# groovy.net
KiCad netlist of a schematic drawn in EAGLE
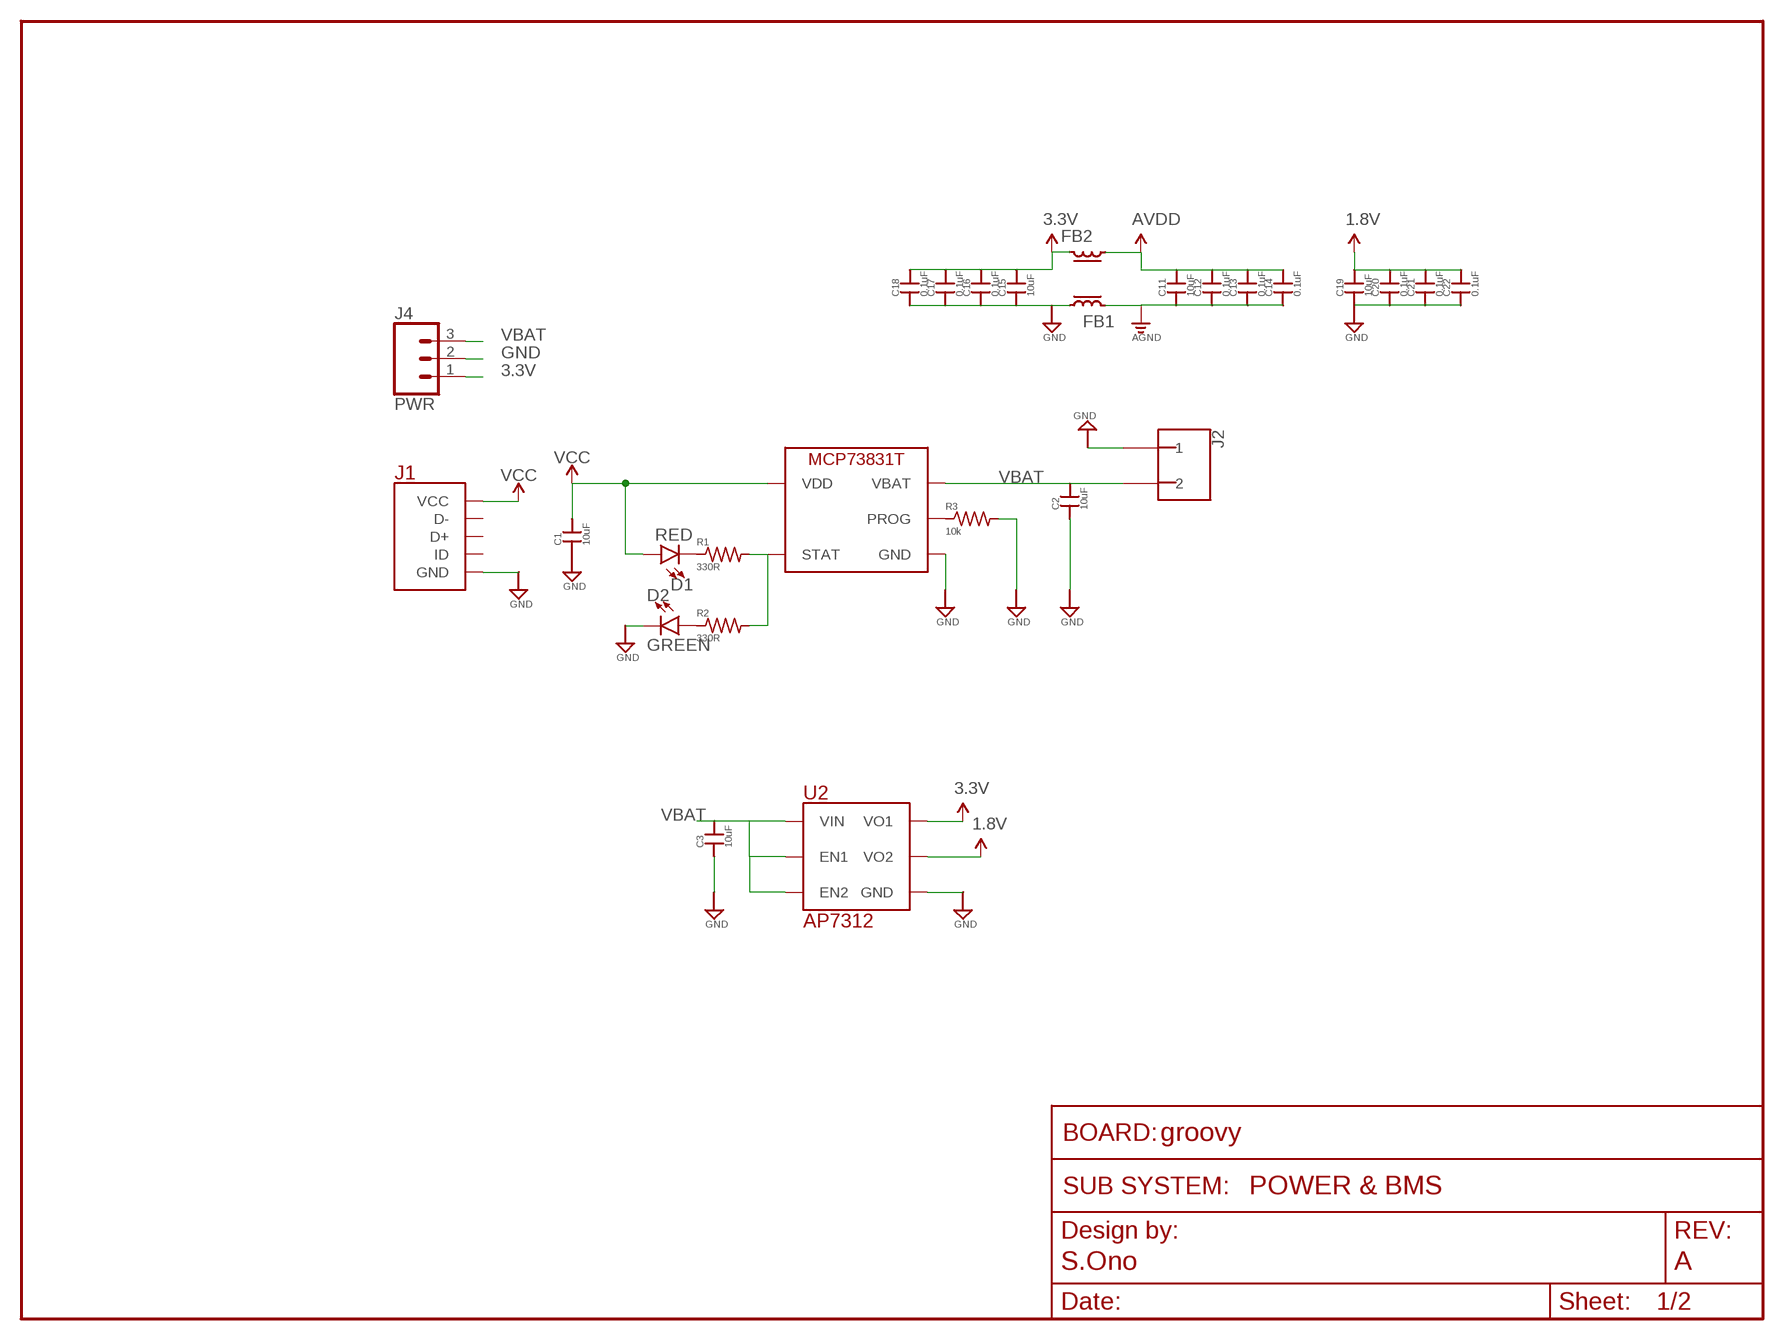
[diagram p0: schematic, sheet 1]
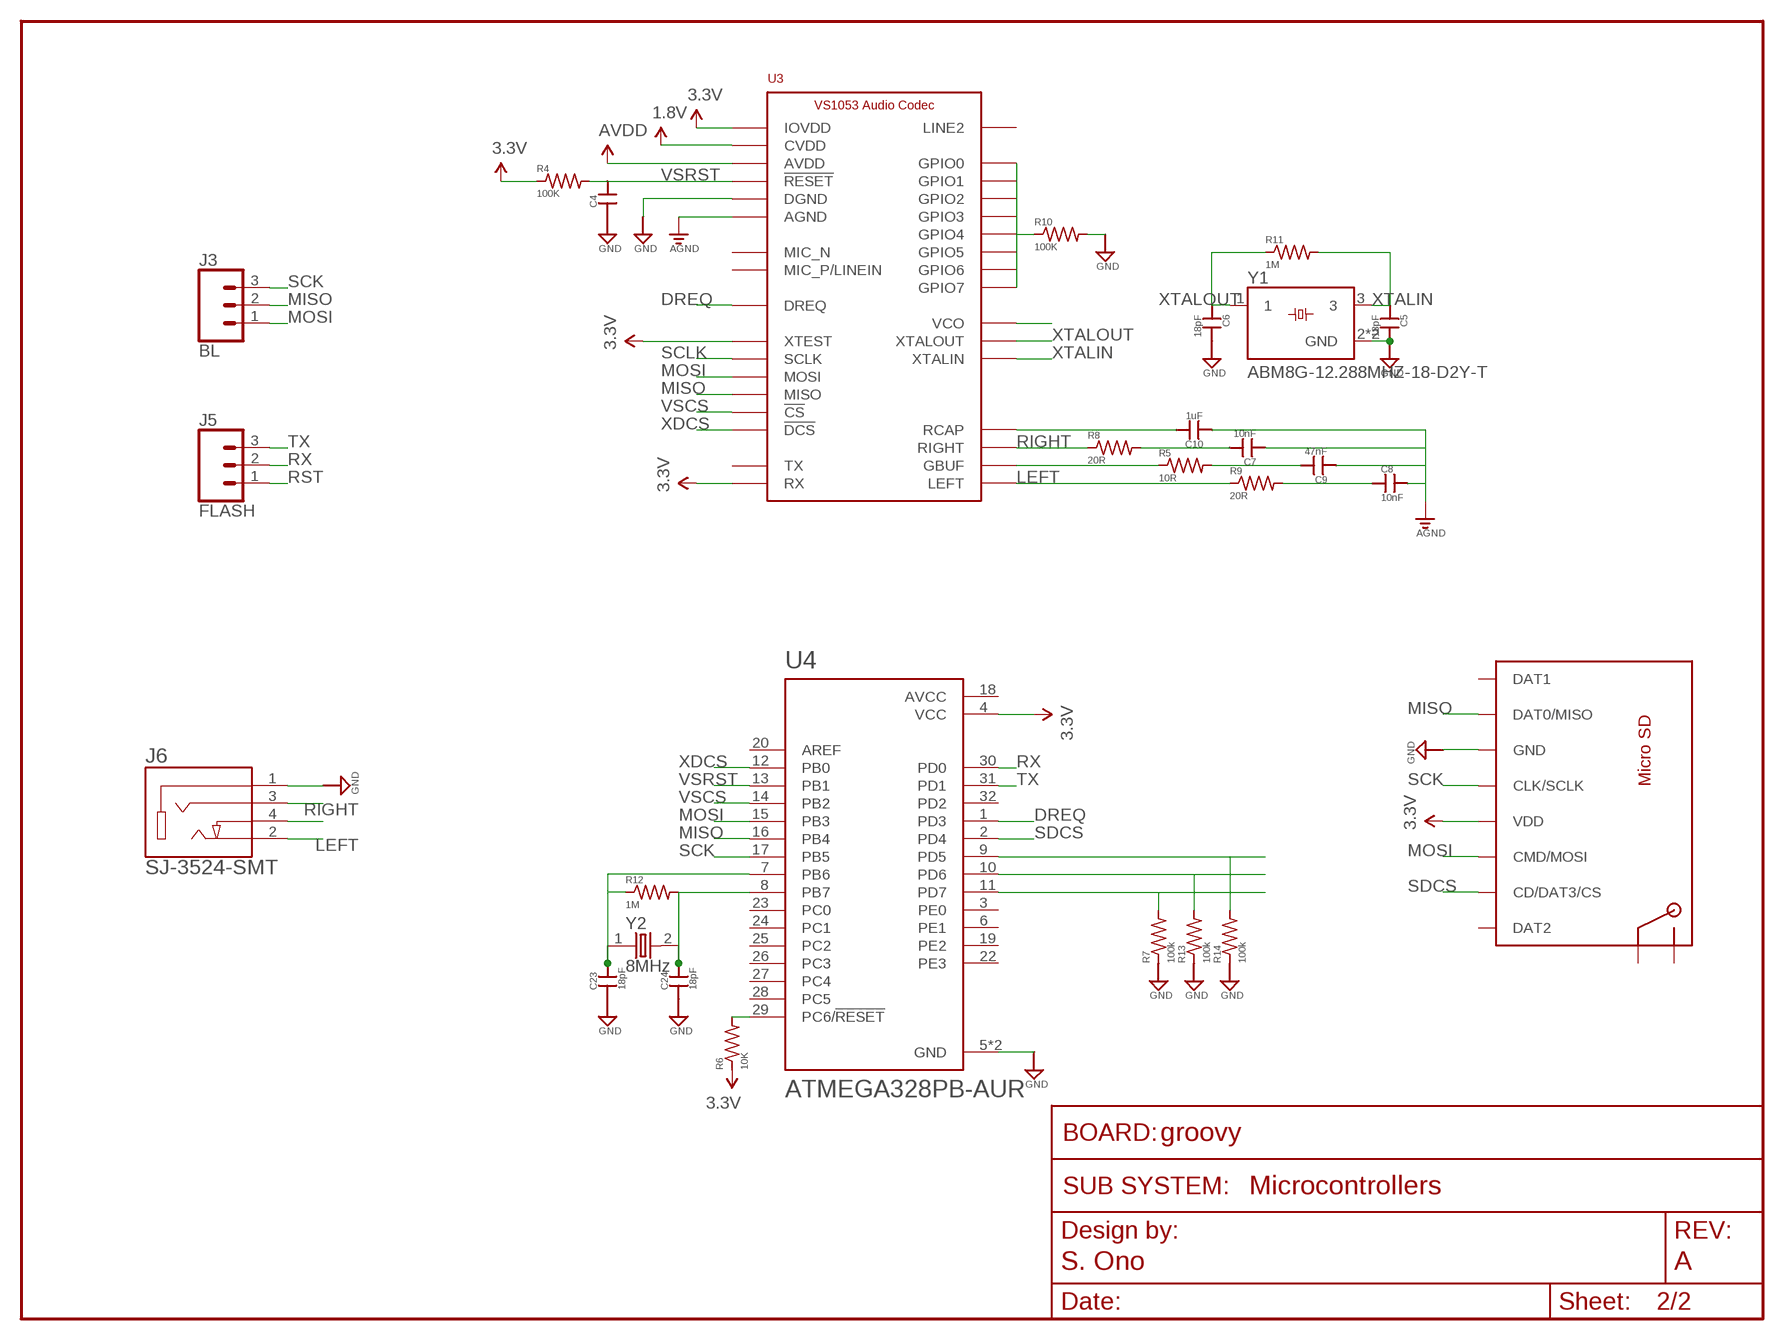
[diagram p1: schematic, sheet 2]

(export (version "E")
  (design (tool "Eeschema 10.0.6"))
  (components
    (comp (ref "C4")
      (value "CAP0603-CAP")
      (footprint "eagle-import:0603-CAP")
      (libsource (lib "eagle-import") (part "CAP0603-CAP"))
    )
    (comp (ref "C5")
      (value "18pF")
      (footprint "eagle-import:0603-CAP")
      (libsource (lib "eagle-import") (part "CAP0603-CAP"))
    )
    (comp (ref "C6")
      (value "18pF")
      (footprint "eagle-import:0603-CAP")
      (libsource (lib "eagle-import") (part "CAP0603-CAP"))
    )
    (comp (ref "C7")
      (value "10nF")
      (footprint "eagle-import:0603-CAP")
      (libsource (lib "eagle-import") (part "CAP0603-CAP"))
    )
    (comp (ref "C8")
      (value "10nF")
      (footprint "eagle-import:0603-CAP")
      (libsource (lib "eagle-import") (part "CAP0603-CAP"))
    )
    (comp (ref "C9")
      (value "47nF")
      (footprint "eagle-import:0603-CAP")
      (libsource (lib "eagle-import") (part "CAP0603-CAP"))
    )
    (comp (ref "C10")
      (value "1uF")
      (footprint "eagle-import:0603-CAP")
      (libsource (lib "eagle-import") (part "CAP0603-CAP"))
    )
    (comp (ref "C23")
      (value "18pF")
      (footprint "eagle-import:0603-CAP")
      (libsource (lib "eagle-import") (part "CAP0603-CAP"))
    )
    (comp (ref "C24")
      (value "18pF")
      (footprint "eagle-import:0603-CAP")
      (libsource (lib "eagle-import") (part "CAP0603-CAP"))
    )
    (comp (ref "J3")
      (value "BL")
      (footprint "eagle-import:1X03")
      (libsource (lib "eagle-import") (part "CONN_03"))
    )
    (comp (ref "J5")
      (value "FLASH")
      (footprint "eagle-import:1X03")
      (libsource (lib "eagle-import") (part "CONN_03"))
    )
    (comp (ref "J6")
      (value "SJ-3524-SMT")
      (footprint "eagle-import:CUI_SJ-3524-SMT")
      (fields
        (field (name "DIGI-KEY_PART_NUMBER") "CP-3524SJCT-ND")
        (field (name "MF") "CUI Inc.")
        (field (name "MP") "SJ-3524-SMT-TR")
      )
      (libsource (lib "eagle-import") (part "SJ-3524-SMT"))
    )
    (comp (ref "P1")
      (value "MICROSD")
      (footprint "eagle-import:MICROSD")
      (libsource (lib "eagle-import") (part "MICROSD"))
    )
    (comp (ref "R4")
      (value "100K")
      (footprint "eagle-import:R0603")
      (fields (field (name "MANUFACTURER") "Rohm Semiconductor"))
      (libsource (lib "eagle-import") (part "R-US_R0603"))
    )
    (comp (ref "R5")
      (value "10R")
      (footprint "eagle-import:R0603")
      (fields (field (name "MANUFACTURER") "Rohm Semiconductor"))
      (libsource (lib "eagle-import") (part "R-US_R0603"))
    )
    (comp (ref "R6")
      (value "10K")
      (footprint "eagle-import:R0603")
      (fields (field (name "MANUFACTURER") "Rohm Semiconductor"))
      (libsource (lib "eagle-import") (part "R-US_R0603"))
    )
    (comp (ref "R7")
      (value "100k")
      (footprint "eagle-import:R0603")
      (fields (field (name "MANUFACTURER") "Rohm Semiconductor"))
      (libsource (lib "eagle-import") (part "R-US_R0603"))
    )
    (comp (ref "R8")
      (value "20R")
      (footprint "eagle-import:R0603")
      (fields (field (name "MANUFACTURER") "Rohm Semiconductor"))
      (libsource (lib "eagle-import") (part "R-US_R0603"))
    )
    (comp (ref "R9")
      (value "20R")
      (footprint "eagle-import:R0603")
      (fields (field (name "MANUFACTURER") "Rohm Semiconductor"))
      (libsource (lib "eagle-import") (part "R-US_R0603"))
    )
    (comp (ref "R10")
      (value "100K")
      (footprint "eagle-import:R0603")
      (fields (field (name "MANUFACTURER") "Rohm Semiconductor"))
      (libsource (lib "eagle-import") (part "R-US_R0603"))
    )
    (comp (ref "R11")
      (value "1M")
      (footprint "eagle-import:R0603")
      (fields (field (name "MANUFACTURER") "Rohm Semiconductor"))
      (libsource (lib "eagle-import") (part "R-US_R0603"))
    )
    (comp (ref "R12")
      (value "1M")
      (footprint "eagle-import:R0603")
      (fields (field (name "MANUFACTURER") "Rohm Semiconductor"))
      (libsource (lib "eagle-import") (part "R-US_R0603"))
    )
    (comp (ref "R13")
      (value "100k")
      (footprint "eagle-import:R0603")
      (fields (field (name "MANUFACTURER") "Rohm Semiconductor"))
      (libsource (lib "eagle-import") (part "R-US_R0603"))
    )
    (comp (ref "R14")
      (value "100k")
      (footprint "eagle-import:R0603")
      (fields (field (name "MANUFACTURER") "Rohm Semiconductor"))
      (libsource (lib "eagle-import") (part "R-US_R0603"))
    )
    (comp (ref "U3")
      (value "VS1053")
      (footprint "eagle-import:QFP50P900X900X120-48N")
      (libsource (lib "eagle-import") (part "VS1053"))
    )
    (comp (ref "U4")
      (value "ATMEGA328PB-AUR")
      (footprint "eagle-import:QFP80P900X900X120-32N")
      (fields (field (name "DIGI-KEY_PART_NUMBER") "ATMEGA328PB-AURCT-ND") (field (name "MF") "Microchip"))
      (libsource (lib "eagle-import") (part "ATMEGA328PB-AUR"))
    )
    (comp (ref "Y1")
      (value "ABM8G-12.288MHZ-18-D2Y-T")
      (footprint "eagle-import:OSCSC320X250X100N")
      (fields (field (name "DIGI-KEY_PART_NUMBER") "535-10262-1-ND") (field (name "MF") "Abracon"))
      (libsource (lib "eagle-import") (part "ABM8G-12.288MHZ-18-D2Y-T"))
    )
    (comp (ref "Y2")
      (value "8MHz")
      (footprint "eagle-import:XTAL500X320X130N")
      (fields
        (field (name "DIGI-KEY_PART_NUMBER") "535-10630-1-ND")
        (field (name "MF") "Abracon")
        (field (name "MP") "ABM3-8.000MHZ-D2Y-T")
      )
      (libsource (lib "eagle-import") (part "ABM3-8.000MHZ-D2Y-T"))
    )
    (comp (ref "C1")
      (value "10uF")
      (footprint "eagle-import:0402-CAP")
      (libsource (lib "eagle-import") (part "CAP0402-CAP"))
    )
    (comp (ref "C2")
      (value "10uF")
      (footprint "eagle-import:0402-CAP")
      (libsource (lib "eagle-import") (part "CAP0402-CAP"))
    )
    (comp (ref "C3")
      (value "10uF")
      (footprint "eagle-import:0402-CAP")
      (libsource (lib "eagle-import") (part "CAP0402-CAP"))
    )
    (comp (ref "C11")
      (value "10uF")
      (footprint "eagle-import:0402-CAP")
      (libsource (lib "eagle-import") (part "CAP0402-CAP"))
    )
    (comp (ref "C12")
      (value "0.1uF")
      (footprint "eagle-import:0402-CAP")
      (libsource (lib "eagle-import") (part "CAP0402-CAP"))
    )
    (comp (ref "C13")
      (value "0.1uF")
      (footprint "eagle-import:0402-CAP")
      (libsource (lib "eagle-import") (part "CAP0402-CAP"))
    )
    (comp (ref "C14")
      (value "0.1uF")
      (footprint "eagle-import:0402-CAP")
      (libsource (lib "eagle-import") (part "CAP0402-CAP"))
    )
    (comp (ref "C15")
      (value "10uF")
      (footprint "eagle-import:0402-CAP")
      (libsource (lib "eagle-import") (part "CAP0402-CAP"))
    )
    (comp (ref "C16")
      (value "0.1uF")
      (footprint "eagle-import:0402-CAP")
      (libsource (lib "eagle-import") (part "CAP0402-CAP"))
    )
    (comp (ref "C17")
      (value "0.1uF")
      (footprint "eagle-import:0402-CAP")
      (libsource (lib "eagle-import") (part "CAP0402-CAP"))
    )
    (comp (ref "C18")
      (value "0.1uF")
      (footprint "eagle-import:0402-CAP")
      (libsource (lib "eagle-import") (part "CAP0402-CAP"))
    )
    (comp (ref "C19")
      (value "10uF")
      (footprint "eagle-import:0402-CAP")
      (libsource (lib "eagle-import") (part "CAP0402-CAP"))
    )
    (comp (ref "C20")
      (value "0.1uF")
      (footprint "eagle-import:0402-CAP")
      (libsource (lib "eagle-import") (part "CAP0402-CAP"))
    )
    (comp (ref "C21")
      (value "0.1uF")
      (footprint "eagle-import:0402-CAP")
      (libsource (lib "eagle-import") (part "CAP0402-CAP"))
    )
    (comp (ref "C22")
      (value "0.1uF")
      (footprint "eagle-import:0402-CAP")
      (libsource (lib "eagle-import") (part "CAP0402-CAP"))
    )
    (comp (ref "D1")
      (value "RED")
      (footprint "eagle-import:LED-0603")
      (libsource (lib "eagle-import") (part "LED0603"))
    )
    (comp (ref "D2")
      (value "GREEN")
      (footprint "eagle-import:LED-0603")
      (libsource (lib "eagle-import") (part "LED0603"))
    )
    (comp (ref "FB1")
      (value "FERRITE")
      (footprint "eagle-import:0603-FERR")
      (libsource (lib "eagle-import") (part "FERRITE"))
    )
    (comp (ref "FB2")
      (value "FERRITE")
      (footprint "eagle-import:0603-FERR")
      (libsource (lib "eagle-import") (part "FERRITE"))
    )
    (comp (ref "J1")
      (value "USB_MICRO")
      (footprint "eagle-import:USB_MICRO")
      (libsource (lib "eagle-import") (part "USB_MICRO"))
    )
    (comp (ref "J2")
      (value "2_PIN_JST-XH")
      (footprint "eagle-import:2_PIN_JST-XH")
      (libsource (lib "eagle-import") (part "2_PIN_JST-XH"))
    )
    (comp (ref "J4")
      (value "PWR")
      (footprint "eagle-import:1X03")
      (libsource (lib "eagle-import") (part "CONN_03"))
    )
    (comp (ref "R1")
      (value "330R")
      (footprint "eagle-import:R0603")
      (fields (field (name "MANUFACTURER") "Rohm Semiconductor"))
      (libsource (lib "eagle-import") (part "R-US_R0603"))
    )
    (comp (ref "R2")
      (value "330R")
      (footprint "eagle-import:R0603")
      (fields (field (name "MANUFACTURER") "Rohm Semiconductor"))
      (libsource (lib "eagle-import") (part "R-US_R0603"))
    )
    (comp (ref "R3")
      (value "10k")
      (footprint "eagle-import:R0603")
      (fields (field (name "MANUFACTURER") "Rohm Semiconductor"))
      (libsource (lib "eagle-import") (part "R-US_R0603"))
    )
    (comp (ref "U1")
      (value "MCP73831T")
      (footprint "eagle-import:SOT23-5")
      (libsource (lib "eagle-import") (part "MCP73831T"))
    )
    (comp (ref "U2")
      (value "AP7312-1833")
      (footprint "eagle-import:6-SOT")
      (libsource (lib "eagle-import") (part "AP7312-1833"))
    )
  )
  (nets
    (net (code "1") (name "1.8V") (class "Default")
      (node (ref "C19") (pin "2") (pinfunction "2_2") (pintype "passive"))
      (node (ref "C20") (pin "2") (pinfunction "2_2") (pintype "passive"))
      (node (ref "C21") (pin "2") (pinfunction "2_2") (pintype "passive"))
      (node (ref "C22") (pin "2") (pinfunction "2_2") (pintype "passive"))
      (node (ref "U2") (pin "1") (pinfunction "VO2_1") (pintype "bidirectional"))
      (node (ref "U3") (pin "24") (pinfunction "CVDD_24") (pintype "bidirectional"))
      (node (ref "U3") (pin "31") (pinfunction "CVDD_31") (pintype "bidirectional"))
      (node (ref "U3") (pin "5") (pinfunction "CVDD_5") (pintype "bidirectional"))
      (node (ref "U3") (pin "7") (pinfunction "CVDD_7") (pintype "bidirectional"))
    )
    (net (code "2") (name "3.3V") (class "Default")
      (node (ref "C15") (pin "2") (pinfunction "2_2") (pintype "passive"))
      (node (ref "C16") (pin "2") (pinfunction "2_2") (pintype "passive"))
      (node (ref "C17") (pin "2") (pinfunction "2_2") (pintype "passive"))
      (node (ref "C18") (pin "2") (pinfunction "2_2") (pintype "passive"))
      (node (ref "FB2") (pin "2") (pinfunction "P$2_2") (pintype "passive"))
      (node (ref "J4") (pin "1") (pinfunction "1_1") (pintype "passive"))
      (node (ref "P1") (pin "4") (pinfunction "VDD_4") (pintype "bidirectional"))
      (node (ref "R4") (pin "1") (pinfunction "1_1") (pintype "passive"))
      (node (ref "R6") (pin "1") (pinfunction "1_1") (pintype "passive"))
      (node (ref "U2") (pin "6") (pinfunction "VO1_6") (pintype "bidirectional"))
      (node (ref "U3") (pin "14") (pinfunction "IOVDD_14") (pintype "bidirectional"))
      (node (ref "U3") (pin "19") (pinfunction "IOVDD_19") (pintype "bidirectional"))
      (node (ref "U3") (pin "26") (pinfunction "RX_26") (pintype "bidirectional"))
      (node (ref "U3") (pin "32") (pinfunction "XTEST_32") (pintype "bidirectional"))
      (node (ref "U3") (pin "6") (pinfunction "IOVDD_6") (pintype "bidirectional"))
      (node (ref "U4") (pin "4") (pinfunction "VCC_4") (pintype "power_in"))
    )
    (net (code "3") (name "AGND") (class "Default")
      (node (ref "C10") (pin "1") (pinfunction "1_1") (pintype "passive"))
      (node (ref "C11") (pin "1") (pinfunction "1_1") (pintype "passive"))
      (node (ref "C12") (pin "1") (pinfunction "1_1") (pintype "passive"))
      (node (ref "C13") (pin "1") (pinfunction "1_1") (pintype "passive"))
      (node (ref "C14") (pin "1") (pinfunction "1_1") (pintype "passive"))
      (node (ref "C7") (pin "1") (pinfunction "1_1") (pintype "passive"))
      (node (ref "C8") (pin "2") (pinfunction "2_2") (pintype "passive"))
      (node (ref "C9") (pin "1") (pinfunction "1_1") (pintype "passive"))
      (node (ref "FB1") (pin "2") (pinfunction "P$2_2") (pintype "passive"))
      (node (ref "U3") (pin "37") (pinfunction "AGND_37") (pintype "bidirectional"))
      (node (ref "U3") (pin "40") (pinfunction "AGND_40") (pintype "bidirectional"))
      (node (ref "U3") (pin "41") (pinfunction "AGND_41") (pintype "bidirectional"))
      (node (ref "U3") (pin "47") (pinfunction "AGND_47") (pintype "bidirectional"))
    )
    (net (code "4") (name "AVCC") (class "Default")
      (node (ref "U4") (pin "18") (pinfunction "AVCC_18") (pintype "power_in"))
    )
    (net (code "5") (name "AVDD") (class "Default")
      (node (ref "C11") (pin "2") (pinfunction "2_2") (pintype "passive"))
      (node (ref "C12") (pin "2") (pinfunction "2_2") (pintype "passive"))
      (node (ref "C13") (pin "2") (pinfunction "2_2") (pintype "passive"))
      (node (ref "C14") (pin "2") (pinfunction "2_2") (pintype "passive"))
      (node (ref "FB2") (pin "1") (pinfunction "P$1_1") (pintype "passive"))
      (node (ref "U3") (pin "38") (pinfunction "AVDD_38") (pintype "bidirectional"))
      (node (ref "U3") (pin "43") (pinfunction "AVDD_43") (pintype "bidirectional"))
      (node (ref "U3") (pin "45") (pinfunction "AVDD_45") (pintype "bidirectional"))
    )
    (net (code "6") (name "DREQ") (class "Default")
      (node (ref "U3") (pin "8") (pinfunction "DREQ_8") (pintype "bidirectional"))
      (node (ref "U4") (pin "1") (pinfunction "PD3_1") (pintype "bidirectional"))
    )
    (net (code "7") (name "GND") (class "Default")
      (node (ref "C1") (pin "1") (pinfunction "1_1") (pintype "passive"))
      (node (ref "C15") (pin "1") (pinfunction "1_1") (pintype "passive"))
      (node (ref "C16") (pin "1") (pinfunction "1_1") (pintype "passive"))
      (node (ref "C17") (pin "1") (pinfunction "1_1") (pintype "passive"))
      (node (ref "C18") (pin "1") (pinfunction "1_1") (pintype "passive"))
      (node (ref "C19") (pin "1") (pinfunction "1_1") (pintype "passive"))
      (node (ref "C2") (pin "1") (pinfunction "1_1") (pintype "passive"))
      (node (ref "C20") (pin "1") (pinfunction "1_1") (pintype "passive"))
      (node (ref "C21") (pin "1") (pinfunction "1_1") (pintype "passive"))
      (node (ref "C22") (pin "1") (pinfunction "1_1") (pintype "passive"))
      (node (ref "C23") (pin "1") (pinfunction "1_1") (pintype "passive"))
      (node (ref "C24") (pin "1") (pinfunction "1_1") (pintype "passive"))
      (node (ref "C3") (pin "1") (pinfunction "1_1") (pintype "passive"))
      (node (ref "C4") (pin "1") (pinfunction "1_1") (pintype "passive"))
      (node (ref "C5") (pin "2") (pinfunction "2_2") (pintype "passive"))
      (node (ref "C6") (pin "2") (pinfunction "2_2") (pintype "passive"))
      (node (ref "D2") (pin "C") (pinfunction "C_C") (pintype "passive"))
      (node (ref "FB1") (pin "1") (pinfunction "P$1_1") (pintype "passive"))
      (node (ref "J1") (pin "GND") (pinfunction "GND_GND") (pintype "bidirectional"))
      (node (ref "J2") (pin "P$1") (pinfunction "1_P$1") (pintype "bidirectional"))
      (node (ref "J4") (pin "2") (pinfunction "2_2") (pintype "passive"))
      (node (ref "J6") (pin "1") (pinfunction "1_1") (pintype "passive"))
      (node (ref "P1") (pin "6") (pinfunction "GND_6") (pintype "bidirectional"))
      (node (ref "R10") (pin "2") (pinfunction "2_2") (pintype "passive"))
      (node (ref "R13") (pin "1") (pinfunction "1_1") (pintype "passive"))
      (node (ref "R14") (pin "1") (pinfunction "1_1") (pintype "passive"))
      (node (ref "R3") (pin "2") (pinfunction "2_2") (pintype "passive"))
      (node (ref "R7") (pin "1") (pinfunction "1_1") (pintype "passive"))
      (node (ref "U1") (pin "2") (pinfunction "GND_2") (pintype "bidirectional"))
      (node (ref "U2") (pin "2") (pinfunction "GND_2") (pintype "bidirectional"))
      (node (ref "U3") (pin "16") (pinfunction "DGND_16") (pintype "bidirectional"))
      (node (ref "U3") (pin "20") (pinfunction "DGND_20") (pintype "bidirectional"))
      (node (ref "U3") (pin "21") (pinfunction "DGND_21") (pintype "bidirectional"))
      (node (ref "U3") (pin "22") (pinfunction "DGND_22") (pintype "bidirectional"))
      (node (ref "U3") (pin "35") (pinfunction "DGND_35") (pintype "bidirectional"))
      (node (ref "U3") (pin "4") (pinfunction "DGND_4") (pintype "bidirectional"))
      (node (ref "U4") (pin "21") (pinfunction "GND_21") (pintype "power_in"))
      (node (ref "U4") (pin "5") (pinfunction "GND_5") (pintype "power_in"))
      (node (ref "Y1") (pin "2") (pinfunction "GND_2") (pintype "power_in"))
      (node (ref "Y1") (pin "4") (pinfunction "GND_4") (pintype "power_in"))
    )
    (net (code "8") (name "LEFT") (class "Default")
      (node (ref "J6") (pin "2") (pinfunction "2_2") (pintype "passive"))
      (node (ref "R9") (pin "1") (pinfunction "1_1") (pintype "passive"))
      (node (ref "U3") (pin "46") (pinfunction "LEFT_46") (pintype "bidirectional"))
    )
    (net (code "9") (name "MISO") (class "Default")
      (node (ref "J3") (pin "2") (pinfunction "2_2") (pintype "passive"))
      (node (ref "P1") (pin "7") (pinfunction "DAT0/MISO_7") (pintype "bidirectional"))
      (node (ref "U3") (pin "30") (pinfunction "MISO_30") (pintype "bidirectional"))
      (node (ref "U4") (pin "16") (pinfunction "PB4_16") (pintype "bidirectional"))
    )
    (net (code "10") (name "MOSI") (class "Default")
      (node (ref "J3") (pin "1") (pinfunction "1_1") (pintype "passive"))
      (node (ref "P1") (pin "3") (pinfunction "CMD/MOSI_3") (pintype "bidirectional"))
      (node (ref "U3") (pin "29") (pinfunction "MOSI_29") (pintype "bidirectional"))
      (node (ref "U4") (pin "15") (pinfunction "PB3_15") (pintype "bidirectional"))
    )
    (net (code "11") (name "Net-(C7-Pad2)") (class "Default")
      (node (ref "C7") (pin "2") (pinfunction "2_2") (pintype "passive"))
      (node (ref "R8") (pin "2") (pinfunction "2_2") (pintype "passive"))
    )
    (net (code "12") (name "Net-(C8-Pad1)") (class "Default")
      (node (ref "C8") (pin "1") (pinfunction "1_1") (pintype "passive"))
      (node (ref "R9") (pin "2") (pinfunction "2_2") (pintype "passive"))
    )
    (net (code "13") (name "Net-(C9-Pad2)") (class "Default")
      (node (ref "C9") (pin "2") (pinfunction "2_2") (pintype "passive"))
      (node (ref "R5") (pin "2") (pinfunction "2_2") (pintype "passive"))
    )
    (net (code "14") (name "Net-(D1-PadC)") (class "Default")
      (node (ref "D1") (pin "C") (pinfunction "C_C") (pintype "passive"))
      (node (ref "R1") (pin "1") (pinfunction "1_1") (pintype "passive"))
    )
    (net (code "15") (name "Net-(D2-PadA)") (class "Default")
      (node (ref "D2") (pin "A") (pinfunction "A_A") (pintype "passive"))
      (node (ref "R2") (pin "1") (pinfunction "1_1") (pintype "passive"))
    )
    (net (code "16") (name "Net-(U1-PROG)") (class "Default")
      (node (ref "R3") (pin "1") (pinfunction "1_1") (pintype "passive"))
      (node (ref "U1") (pin "5") (pinfunction "PROG_5") (pintype "bidirectional"))
    )
    (net (code "17") (name "Net-(U1-STAT)") (class "Default")
      (node (ref "R1") (pin "2") (pinfunction "2_2") (pintype "passive"))
      (node (ref "R2") (pin "2") (pinfunction "2_2") (pintype "passive"))
      (node (ref "U1") (pin "1") (pinfunction "STAT_1") (pintype "bidirectional"))
    )
    (net (code "18") (name "Net-(U3-GBUF)") (class "Default")
      (node (ref "R5") (pin "1") (pinfunction "1_1") (pintype "passive"))
      (node (ref "U3") (pin "42") (pinfunction "GBUF_42") (pintype "bidirectional"))
    )
    (net (code "19") (name "Net-(U3-GPIO0)") (class "Default")
      (node (ref "R10") (pin "1") (pinfunction "1_1") (pintype "passive"))
      (node (ref "U3") (pin "10") (pinfunction "GPIO3_10") (pintype "bidirectional"))
      (node (ref "U3") (pin "11") (pinfunction "GPIO6_11") (pintype "bidirectional"))
      (node (ref "U3") (pin "12") (pinfunction "GPIO7_12") (pintype "bidirectional"))
      (node (ref "U3") (pin "25") (pinfunction "GPIO5_25") (pintype "bidirectional"))
      (node (ref "U3") (pin "33") (pinfunction "GPIO0_33") (pintype "bidirectional"))
      (node (ref "U3") (pin "34") (pinfunction "GPIO1_34") (pintype "bidirectional"))
      (node (ref "U3") (pin "36") (pinfunction "GPIO4_36") (pintype "bidirectional"))
      (node (ref "U3") (pin "9") (pinfunction "GPIO2_9") (pintype "bidirectional"))
    )
    (net (code "20") (name "Net-(U3-RCAP)") (class "Default")
      (node (ref "C10") (pin "2") (pinfunction "2_2") (pintype "passive"))
      (node (ref "U3") (pin "44") (pinfunction "RCAP_44") (pintype "bidirectional"))
    )
    (net (code "21") (name "Net-(U4-PB6)") (class "Default")
      (node (ref "C23") (pin "2") (pinfunction "2_2") (pintype "passive"))
      (node (ref "R12") (pin "1") (pinfunction "1_1") (pintype "passive"))
      (node (ref "U4") (pin "7") (pinfunction "PB6_7") (pintype "bidirectional"))
      (node (ref "Y2") (pin "1") (pinfunction "1_1") (pintype "passive"))
    )
    (net (code "22") (name "Net-(U4-PB7)") (class "Default")
      (node (ref "C24") (pin "2") (pinfunction "2_2") (pintype "passive"))
      (node (ref "R12") (pin "2") (pinfunction "2_2") (pintype "passive"))
      (node (ref "U4") (pin "8") (pinfunction "PB7_8") (pintype "bidirectional"))
      (node (ref "Y2") (pin "2") (pinfunction "2_2") (pintype "passive"))
    )
    (net (code "23") (name "Net-(U4-PD5)") (class "Default")
      (node (ref "R14") (pin "2") (pinfunction "2_2") (pintype "passive"))
      (node (ref "U4") (pin "9") (pinfunction "PD5_9") (pintype "bidirectional"))
    )
    (net (code "24") (name "Net-(U4-PD6)") (class "Default")
      (node (ref "R13") (pin "2") (pinfunction "2_2") (pintype "passive"))
      (node (ref "U4") (pin "10") (pinfunction "PD6_10") (pintype "bidirectional"))
    )
    (net (code "25") (name "Net-(U4-PD7)") (class "Default")
      (node (ref "R7") (pin "2") (pinfunction "2_2") (pintype "passive"))
      (node (ref "U4") (pin "11") (pinfunction "PD7_11") (pintype "bidirectional"))
    )
    (net (code "26") (name "RIGHT") (class "Default")
      (node (ref "J6") (pin "3") (pinfunction "3_3") (pintype "passive"))
      (node (ref "R8") (pin "1") (pinfunction "1_1") (pintype "passive"))
      (node (ref "U3") (pin "39") (pinfunction "RIGHT_39") (pintype "bidirectional"))
    )
    (net (code "27") (name "RST") (class "Default")
      (node (ref "J5") (pin "1") (pinfunction "1_1") (pintype "passive"))
      (node (ref "R6") (pin "2") (pinfunction "2_2") (pintype "passive"))
      (node (ref "U4") (pin "29") (pinfunction "PC6/~{RESET}_29") (pintype "bidirectional"))
    )
    (net (code "28") (name "RX") (class "Default")
      (node (ref "J5") (pin "2") (pinfunction "2_2") (pintype "passive"))
      (node (ref "U4") (pin "30") (pinfunction "PD0_30") (pintype "bidirectional"))
    )
    (net (code "29") (name "SCK") (class "Default")
      (node (ref "J3") (pin "3") (pinfunction "3_3") (pintype "passive"))
      (node (ref "P1") (pin "5") (pinfunction "CLK/SCLK_5") (pintype "bidirectional"))
      (node (ref "U4") (pin "17") (pinfunction "PB5_17") (pintype "bidirectional"))
    )
    (net (code "30") (name "SCLK") (class "Default")
      (node (ref "U3") (pin "28") (pinfunction "SCLK_28") (pintype "bidirectional"))
    )
    (net (code "31") (name "SDCS") (class "Default")
      (node (ref "P1") (pin "2") (pinfunction "CD/DAT3/CS_2") (pintype "bidirectional"))
      (node (ref "U4") (pin "2") (pinfunction "PD4_2") (pintype "bidirectional"))
    )
    (net (code "32") (name "TX") (class "Default")
      (node (ref "J5") (pin "3") (pinfunction "3_3") (pintype "passive"))
      (node (ref "U4") (pin "31") (pinfunction "PD1_31") (pintype "bidirectional"))
    )
    (net (code "33") (name "VBAT") (class "Default")
      (node (ref "C2") (pin "2") (pinfunction "2_2") (pintype "passive"))
      (node (ref "C3") (pin "2") (pinfunction "2_2") (pintype "passive"))
      (node (ref "J2") (pin "P$2") (pinfunction "2_P$2") (pintype "bidirectional"))
      (node (ref "J4") (pin "3") (pinfunction "3_3") (pintype "passive"))
      (node (ref "U1") (pin "3") (pinfunction "VBAT_3") (pintype "bidirectional"))
      (node (ref "U2") (pin "3") (pinfunction "EN2_3") (pintype "bidirectional"))
      (node (ref "U2") (pin "4") (pinfunction "EN1_4") (pintype "bidirectional"))
      (node (ref "U2") (pin "5") (pinfunction "VIN_5") (pintype "bidirectional"))
    )
    (net (code "34") (name "VCC") (class "Default")
      (node (ref "C1") (pin "2") (pinfunction "2_2") (pintype "passive"))
      (node (ref "D1") (pin "A") (pinfunction "A_A") (pintype "passive"))
      (node (ref "J1") (pin "VCC") (pinfunction "VCC_VCC") (pintype "bidirectional"))
      (node (ref "U1") (pin "4") (pinfunction "VDD_4") (pintype "bidirectional"))
    )
    (net (code "35") (name "VSCS") (class "Default")
      (node (ref "U3") (pin "23") (pinfunction "~{CS}_23") (pintype "bidirectional"))
      (node (ref "U4") (pin "14") (pinfunction "PB2_14") (pintype "bidirectional"))
    )
    (net (code "36") (name "VSRST") (class "Default")
      (node (ref "C4") (pin "2") (pinfunction "2_2") (pintype "passive"))
      (node (ref "R4") (pin "2") (pinfunction "2_2") (pintype "passive"))
      (node (ref "U3") (pin "3") (pinfunction "~{RESET}_3") (pintype "bidirectional"))
      (node (ref "U4") (pin "13") (pinfunction "PB1_13") (pintype "bidirectional"))
    )
    (net (code "37") (name "XDCS") (class "Default")
      (node (ref "U3") (pin "13") (pinfunction "~{DCS}_13") (pintype "bidirectional"))
      (node (ref "U4") (pin "12") (pinfunction "PB0_12") (pintype "bidirectional"))
    )
    (net (code "38") (name "XTALIN") (class "Default")
      (node (ref "C5") (pin "1") (pinfunction "1_1") (pintype "passive"))
      (node (ref "R11") (pin "2") (pinfunction "2_2") (pintype "passive"))
      (node (ref "U3") (pin "18") (pinfunction "XTALIN_18") (pintype "bidirectional"))
      (node (ref "Y1") (pin "3") (pinfunction "3_3") (pintype "passive"))
    )
    (net (code "39") (name "XTALOUT") (class "Default")
      (node (ref "C6") (pin "1") (pinfunction "1_1") (pintype "passive"))
      (node (ref "R11") (pin "1") (pinfunction "1_1") (pintype "passive"))
      (node (ref "U3") (pin "17") (pinfunction "XTALOUT_17") (pintype "bidirectional"))
      (node (ref "Y1") (pin "1") (pinfunction "1_1") (pintype "passive"))
    )
    (net (code "40") (name "unconnected-(J1-PadD+)") (class "Default")
      (node (ref "J1") (pin "D+") (pinfunction "D+_D+") (pintype "bidirectional"))
    )
    (net (code "41") (name "unconnected-(J1-PadD-)") (class "Default")
      (node (ref "J1") (pin "D-") (pinfunction "D-_D-") (pintype "bidirectional"))
    )
    (net (code "42") (name "unconnected-(J1-PadID)") (class "Default")
      (node (ref "J1") (pin "ID") (pinfunction "ID_ID") (pintype "bidirectional"))
    )
    (net (code "43") (name "unconnected-(J6-Pad4)") (class "Default")
      (node (ref "J6") (pin "4") (pinfunction "4_4") (pintype "passive"))
    )
    (net (code "44") (name "unconnected-(P1-DAT1-Pad8)") (class "Default")
      (node (ref "P1") (pin "8") (pinfunction "DAT1_8") (pintype "bidirectional"))
    )
    (net (code "45") (name "unconnected-(P1-DAT2-Pad1)") (class "Default")
      (node (ref "P1") (pin "1") (pinfunction "DAT2_1") (pintype "bidirectional"))
    )
    (net (code "46") (name "unconnected-(P1-DET0-PadDETECT1)") (class "Default")
      (node (ref "P1") (pin "DETECT1") (pinfunction "DET0_DETECT1") (pintype "bidirectional"))
    )
    (net (code "47") (name "unconnected-(P1-DET1-PadDETECT2)") (class "Default")
      (node (ref "P1") (pin "DETECT2") (pinfunction "DET1_DETECT2") (pintype "bidirectional"))
    )
    (net (code "48") (name "unconnected-(U3-LINE2-Pad48)") (class "Default")
      (node (ref "U3") (pin "48") (pinfunction "LINE2_48") (pintype "bidirectional"))
    )
    (net (code "49") (name "unconnected-(U3-MIC_N-Pad2)") (class "Default")
      (node (ref "U3") (pin "2") (pinfunction "MIC_N_2") (pintype "bidirectional"))
    )
    (net (code "50") (name "unconnected-(U3-MIC_P{slash}LINEIN-Pad1)") (class "Default")
      (node (ref "U3") (pin "1") (pinfunction "MIC_P/LINEIN_1") (pintype "bidirectional"))
    )
    (net (code "51") (name "unconnected-(U3-TX-Pad27)") (class "Default")
      (node (ref "U3") (pin "27") (pinfunction "TX_27") (pintype "bidirectional"))
    )
    (net (code "52") (name "unconnected-(U3-VCO-Pad15)") (class "Default")
      (node (ref "U3") (pin "15") (pinfunction "VCO_15") (pintype "bidirectional"))
    )
    (net (code "53") (name "unconnected-(U4-AREF-Pad20)") (class "Default")
      (node (ref "U4") (pin "20") (pinfunction "AREF_20") (pintype "input"))
    )
    (net (code "54") (name "unconnected-(U4-PC0-Pad23)") (class "Default")
      (node (ref "U4") (pin "23") (pinfunction "PC0_23") (pintype "bidirectional"))
    )
    (net (code "55") (name "unconnected-(U4-PC1-Pad24)") (class "Default")
      (node (ref "U4") (pin "24") (pinfunction "PC1_24") (pintype "bidirectional"))
    )
    (net (code "56") (name "unconnected-(U4-PC2-Pad25)") (class "Default")
      (node (ref "U4") (pin "25") (pinfunction "PC2_25") (pintype "bidirectional"))
    )
    (net (code "57") (name "unconnected-(U4-PC3-Pad26)") (class "Default")
      (node (ref "U4") (pin "26") (pinfunction "PC3_26") (pintype "bidirectional"))
    )
    (net (code "58") (name "unconnected-(U4-PC4-Pad27)") (class "Default")
      (node (ref "U4") (pin "27") (pinfunction "PC4_27") (pintype "bidirectional"))
    )
    (net (code "59") (name "unconnected-(U4-PC5-Pad28)") (class "Default")
      (node (ref "U4") (pin "28") (pinfunction "PC5_28") (pintype "bidirectional"))
    )
    (net (code "60") (name "unconnected-(U4-PD2-Pad32)") (class "Default")
      (node (ref "U4") (pin "32") (pinfunction "PD2_32") (pintype "bidirectional"))
    )
    (net (code "61") (name "unconnected-(U4-PE0-Pad3)") (class "Default")
      (node (ref "U4") (pin "3") (pinfunction "PE0_3") (pintype "bidirectional"))
    )
    (net (code "62") (name "unconnected-(U4-PE1-Pad6)") (class "Default")
      (node (ref "U4") (pin "6") (pinfunction "PE1_6") (pintype "bidirectional"))
    )
    (net (code "63") (name "unconnected-(U4-PE2-Pad19)") (class "Default")
      (node (ref "U4") (pin "19") (pinfunction "PE2_19") (pintype "bidirectional"))
    )
    (net (code "64") (name "unconnected-(U4-PE3-Pad22)") (class "Default")
      (node (ref "U4") (pin "22") (pinfunction "PE3_22") (pintype "bidirectional"))
    )
  )
)
